# design.net
KiCad netlist of a schematic drawn in Altium Designer
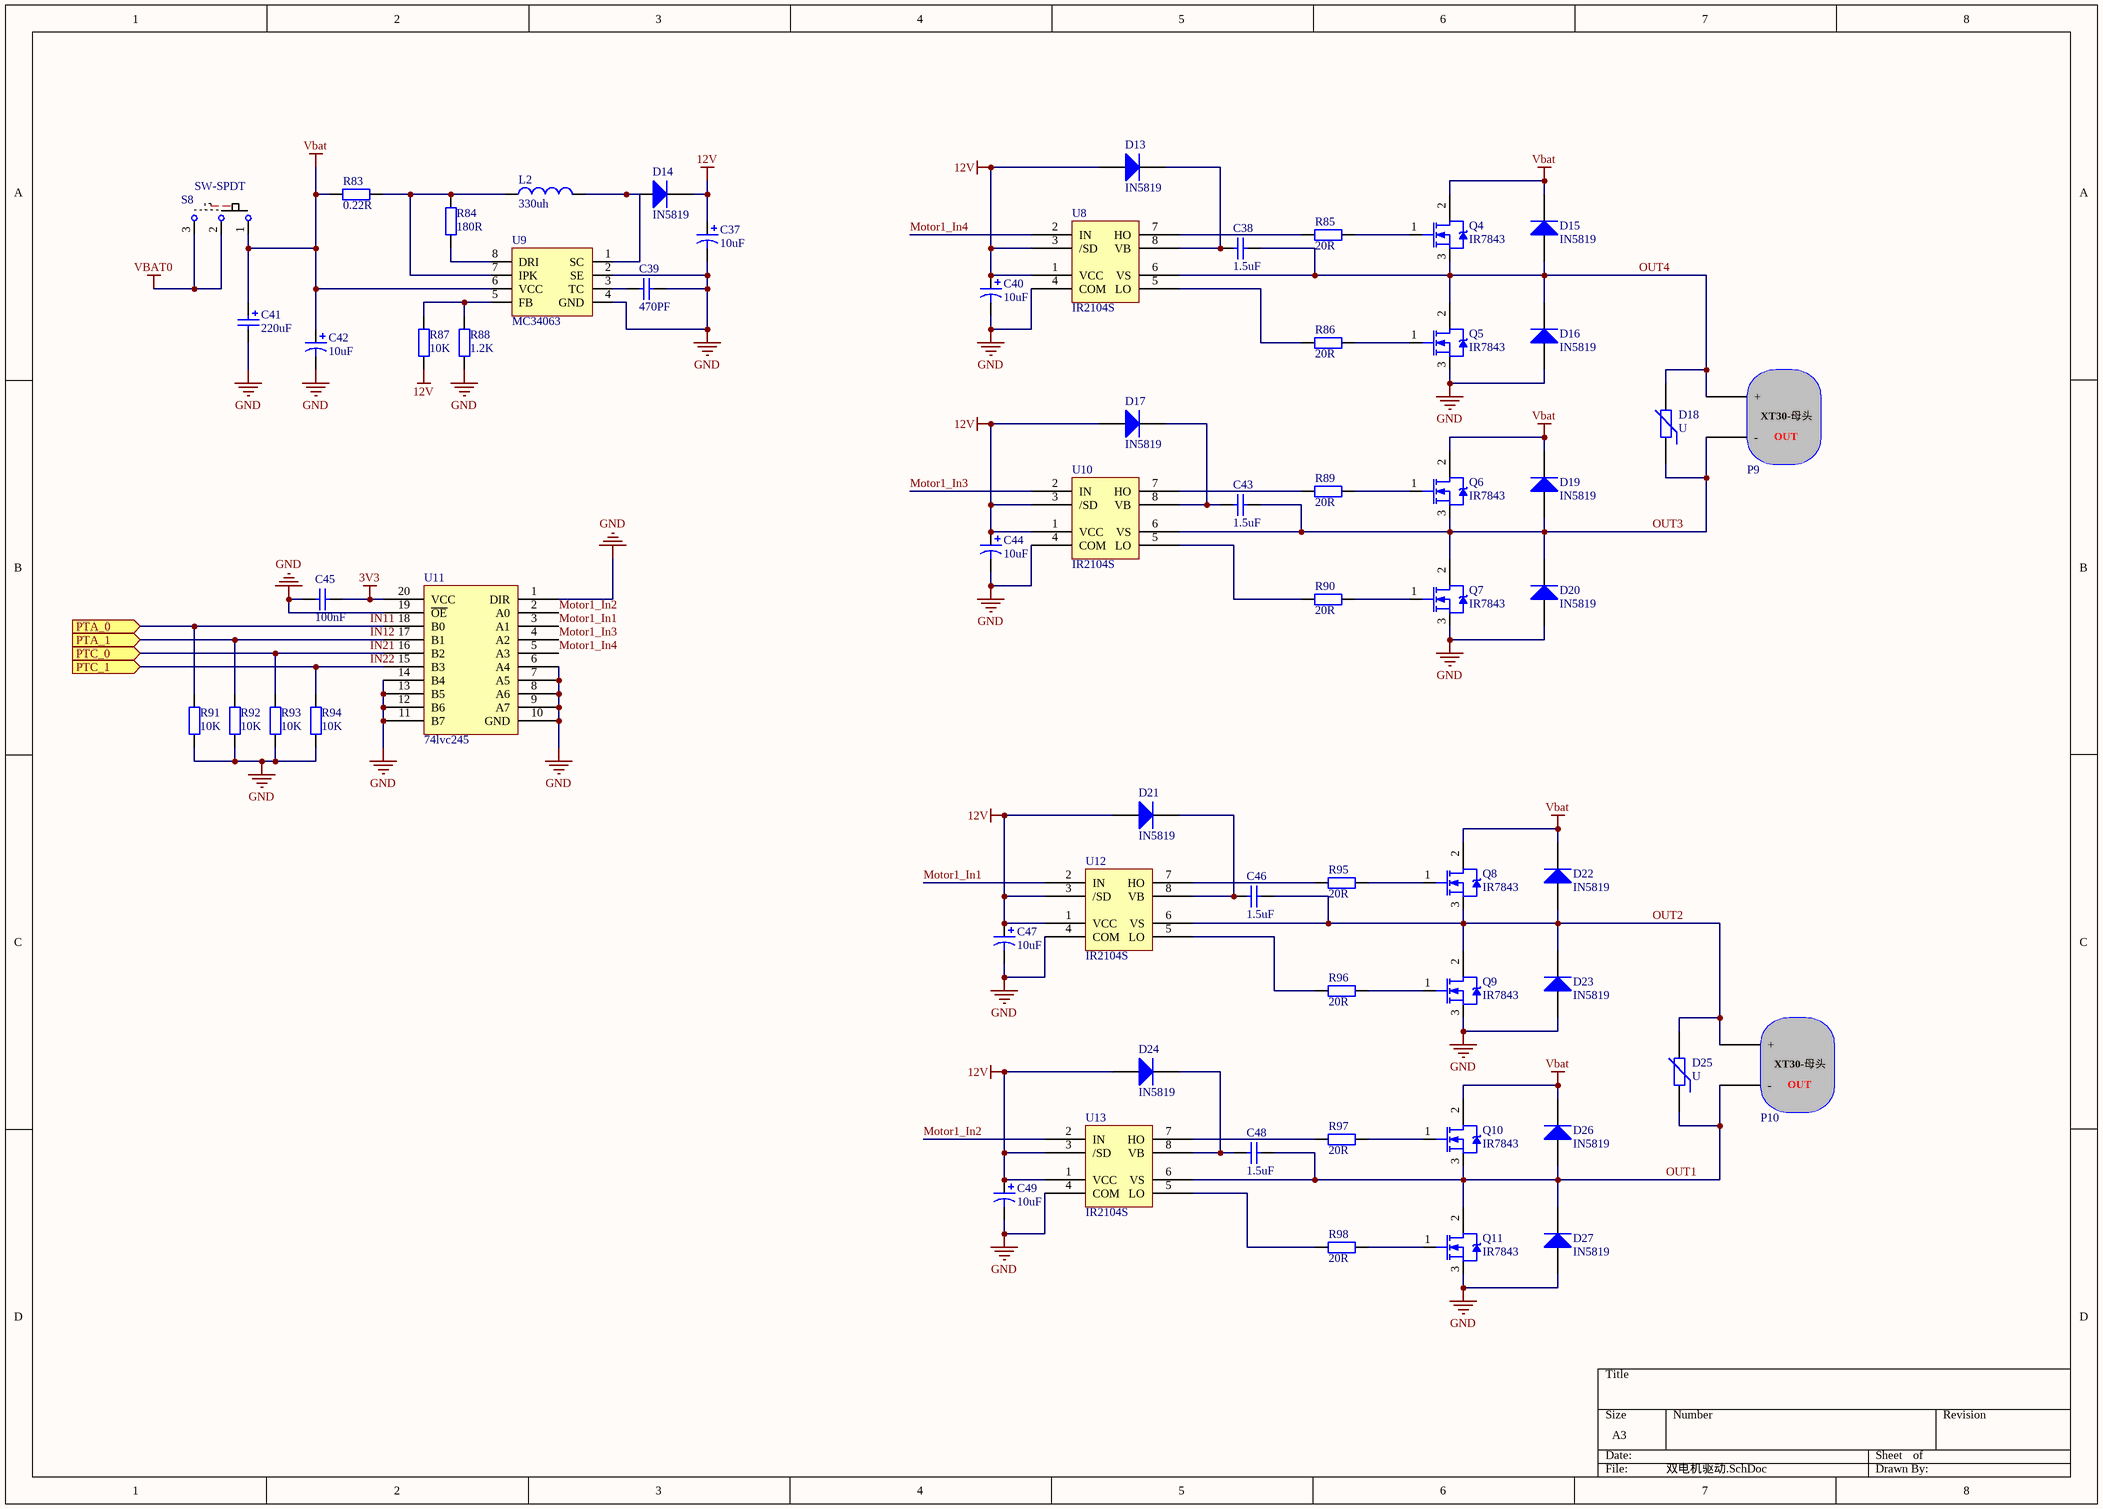
[diagram p0: 双电机驱动.SchDoc]

(export (version "E")
  (design (tool "Eeschema 10.0.6"))
  (components
    (comp (ref "C37")
      (value "10uF")
      (footprint "1206C")
      (description "Polarized Capacitor (Radial)")
      (fields (field (name "PUBLISHER") "Altium Limited"))
      (libsource (lib "MOS motor driving module ") (part "Cap Pol1"))
    )
    (comp (ref "C38")
      (value "1.5uF")
      (footprint "0805(2012)")
      (description "Capacitor")
      (fields (field (name "PUBLISHER") "Altium Limited"))
      (libsource (lib "MOS motor driving module ") (part "Cap"))
    )
    (comp (ref "C39")
      (value "470PF")
      (footprint "0805(2012)")
      (description "Capacitor")
      (fields (field (name "PUBLISHER") "Altium Limited"))
      (libsource (lib "MOS motor driving module ") (part "Cap"))
    )
    (comp (ref "C40")
      (value "10uF")
      (footprint "1206C")
      (description "Polarized Capacitor (Radial)")
      (fields (field (name "PUBLISHER") "Altium Limited"))
      (libsource (lib "MOS motor driving module ") (part "Cap Pol1"))
    )
    (comp (ref "C41")
      (value "220uF")
      (footprint "AEC_D6.3")
      (description "Polarized Capacitor (Radial)")
      (libsource (lib "Landzo电源模块V3.0") (part "Cap Pol1"))
    )
    (comp (ref "C42")
      (value "10uF")
      (footprint "1206C")
      (description "Polarized Capacitor (Radial)")
      (fields (field (name "PUBLISHER") "Altium Limited"))
      (libsource (lib "MOS motor driving module ") (part "Cap Pol1"))
    )
    (comp (ref "C43")
      (value "1.5uF")
      (footprint "0805(2012)")
      (description "Capacitor")
      (fields (field (name "PUBLISHER") "Altium Limited"))
      (libsource (lib "MOS motor driving module ") (part "Cap"))
    )
    (comp (ref "C44")
      (value "10uF")
      (footprint "1206C")
      (description "Polarized Capacitor (Radial)")
      (fields (field (name "PUBLISHER") "Altium Limited"))
      (libsource (lib "MOS motor driving module ") (part "Cap Pol1"))
    )
    (comp (ref "C45")
      (value "100nF")
      (footprint "0805")
      (description "Capacitor")
      (libsource (lib "Landzo电源模块V3.0") (part "Cap"))
    )
    (comp (ref "C46")
      (value "1.5uF")
      (footprint "0805(2012)")
      (description "Capacitor")
      (fields (field (name "PUBLISHER") "Altium Limited"))
      (libsource (lib "MOS motor driving module ") (part "Cap"))
    )
    (comp (ref "C47")
      (value "10uF")
      (footprint "1206C")
      (description "Polarized Capacitor (Radial)")
      (fields (field (name "PUBLISHER") "Altium Limited"))
      (libsource (lib "MOS motor driving module ") (part "Cap Pol1"))
    )
    (comp (ref "C48")
      (value "1.5uF")
      (footprint "0805(2012)")
      (description "Capacitor")
      (fields (field (name "PUBLISHER") "Altium Limited"))
      (libsource (lib "MOS motor driving module ") (part "Cap"))
    )
    (comp (ref "C49")
      (value "10uF")
      (footprint "1206C")
      (description "Polarized Capacitor (Radial)")
      (fields (field (name "PUBLISHER") "Altium Limited"))
      (libsource (lib "MOS motor driving module ") (part "Cap Pol1"))
    )
    (comp (ref "D13")
      (value "IN5819")
      (footprint "Diode-1206")
      (description "Default Diode")
      (libsource (lib "MOS motor driving module ") (part "Diode"))
    )
    (comp (ref "D14")
      (value "IN5819")
      (footprint "SMB")
      (description "Default Diode")
      (libsource (lib "MOS motor driving module ") (part "Diode"))
    )
    (comp (ref "D15")
      (value "IN5819")
      (footprint "SMB")
      (description "Default Diode")
      (libsource (lib "MOS motor driving module ") (part "Diode"))
    )
    (comp (ref "D16")
      (value "IN5819")
      (footprint "SMB")
      (description "Default Diode")
      (libsource (lib "MOS motor driving module ") (part "Diode"))
    )
    (comp (ref "D17")
      (value "IN5819")
      (footprint "Diode-1206")
      (description "Default Diode")
      (libsource (lib "MOS motor driving module ") (part "Diode"))
    )
    (comp (ref "D18")
      (value "U")
      (footprint "0805(2012)")
      (description "Varistor (Voltage-Sensitive Resistor)")
      (fields (field (name "PUBLISHER") "Altium Limited"))
      (libsource (lib "MOS motor driving module ") (part "Res Varistor"))
    )
    (comp (ref "D19")
      (value "IN5819")
      (footprint "SMB")
      (description "Default Diode")
      (libsource (lib "MOS motor driving module ") (part "Diode"))
    )
    (comp (ref "D20")
      (value "IN5819")
      (footprint "SMB")
      (description "Default Diode")
      (libsource (lib "MOS motor driving module ") (part "Diode"))
    )
    (comp (ref "D21")
      (value "IN5819")
      (footprint "Diode-1206")
      (description "Default Diode")
      (libsource (lib "MOS motor driving module ") (part "Diode"))
    )
    (comp (ref "D22")
      (value "IN5819")
      (footprint "SMB")
      (description "Default Diode")
      (libsource (lib "MOS motor driving module ") (part "Diode"))
    )
    (comp (ref "D23")
      (value "IN5819")
      (footprint "SMB")
      (description "Default Diode")
      (libsource (lib "MOS motor driving module ") (part "Diode"))
    )
    (comp (ref "D24")
      (value "IN5819")
      (footprint "Diode-1206")
      (description "Default Diode")
      (libsource (lib "MOS motor driving module ") (part "Diode"))
    )
    (comp (ref "D25")
      (value "U")
      (footprint "0805(2012)")
      (description "Varistor (Voltage-Sensitive Resistor)")
      (fields (field (name "PUBLISHER") "Altium Limited"))
      (libsource (lib "MOS motor driving module ") (part "Res Varistor"))
    )
    (comp (ref "D26")
      (value "IN5819")
      (footprint "SMB")
      (description "Default Diode")
      (libsource (lib "MOS motor driving module ") (part "Diode"))
    )
    (comp (ref "D27")
      (value "IN5819")
      (footprint "SMB")
      (description "Default Diode")
      (libsource (lib "MOS motor driving module ") (part "Diode"))
    )
    (comp (ref "L2")
      (value "330uh")
      (footprint "电感8*8_0")
      (description "Inductor")
      (fields (field (name "PUBLISHER") "Altium Limited"))
      (libsource (lib "MOS motor driving module ") (part "Inductor"))
    )
    (comp (ref "P9") (value "XT30-母-pcb") (footprint "XT30-垂直") (libsource (lib "我的原理图库") (part "XT30-母头")))
    (comp (ref "P10") (value "XT30-母-pcb") (footprint "XT30-垂直") (libsource (lib "我的原理图库") (part "XT30-母头")))
    (comp (ref "Q4")
      (value "IR7843")
      (footprint "LR7843_0")
      (description "N-Channel Power MOSFET")
      (fields (field (name "PUBLISHER") "Altium Limited"))
      (libsource (lib "MOS motor driving module ") (part "NMOS-2"))
    )
    (comp (ref "Q5")
      (value "IR7843")
      (footprint "LR7843_0")
      (description "N-Channel Power MOSFET")
      (fields (field (name "PUBLISHER") "Altium Limited"))
      (libsource (lib "MOS motor driving module ") (part "NMOS-2"))
    )
    (comp (ref "Q6")
      (value "IR7843")
      (footprint "LR7843_0")
      (description "N-Channel Power MOSFET")
      (fields (field (name "PUBLISHER") "Altium Limited"))
      (libsource (lib "MOS motor driving module ") (part "NMOS-2"))
    )
    (comp (ref "Q7")
      (value "IR7843")
      (footprint "LR7843_0")
      (description "N-Channel Power MOSFET")
      (fields (field (name "PUBLISHER") "Altium Limited"))
      (libsource (lib "MOS motor driving module ") (part "NMOS-2"))
    )
    (comp (ref "Q8")
      (value "IR7843")
      (footprint "LR7843_0")
      (description "N-Channel Power MOSFET")
      (fields (field (name "PUBLISHER") "Altium Limited"))
      (libsource (lib "MOS motor driving module ") (part "NMOS-2"))
    )
    (comp (ref "Q9")
      (value "IR7843")
      (footprint "LR7843_0")
      (description "N-Channel Power MOSFET")
      (fields (field (name "PUBLISHER") "Altium Limited"))
      (libsource (lib "MOS motor driving module ") (part "NMOS-2"))
    )
    (comp (ref "Q10")
      (value "IR7843")
      (footprint "LR7843_0")
      (description "N-Channel Power MOSFET")
      (fields (field (name "PUBLISHER") "Altium Limited"))
      (libsource (lib "MOS motor driving module ") (part "NMOS-2"))
    )
    (comp (ref "Q11")
      (value "IR7843")
      (footprint "LR7843_0")
      (description "N-Channel Power MOSFET")
      (fields (field (name "PUBLISHER") "Altium Limited"))
      (libsource (lib "MOS motor driving module ") (part "NMOS-2"))
    )
    (comp (ref "R83")
      (value "0.22R")
      (footprint "0805")
      (description "Resistor")
      (libsource (lib "") (part "Res_3"))
    )
    (comp (ref "R84")
      (value "180R")
      (footprint "0805")
      (description "Resistor")
      (libsource (lib "") (part "Res_1"))
    )
    (comp (ref "R85")
      (value "20R")
      (footprint "0805")
      (description "Resistor")
      (libsource (lib "Landzo电源模块V3.0") (part "Res"))
    )
    (comp (ref "R86")
      (value "20R")
      (footprint "0805")
      (description "Resistor")
      (libsource (lib "Landzo电源模块V3.0") (part "Res"))
    )
    (comp (ref "R87")
      (value "10K")
      (footprint "0805")
      (description "Resistor")
      (libsource (lib "") (part "Res_2"))
    )
    (comp (ref "R88")
      (value "1.2K")
      (footprint "0805")
      (description "Resistor")
      (libsource (lib "") (part "Res_2"))
    )
    (comp (ref "R89")
      (value "20R")
      (footprint "0805")
      (description "Resistor")
      (libsource (lib "Landzo电源模块V3.0") (part "Res"))
    )
    (comp (ref "R90")
      (value "20R")
      (footprint "0805")
      (description "Resistor")
      (libsource (lib "Landzo电源模块V3.0") (part "Res"))
    )
    (comp (ref "R91")
      (value "10K")
      (footprint "0805")
      (description "Resistor")
      (libsource (lib "") (part "Res_1"))
    )
    (comp (ref "R92")
      (value "10K")
      (footprint "0805")
      (description "Resistor")
      (libsource (lib "") (part "Res_1"))
    )
    (comp (ref "R93")
      (value "10K")
      (footprint "0805")
      (description "Resistor")
      (libsource (lib "") (part "Res_1"))
    )
    (comp (ref "R94")
      (value "10K")
      (footprint "0805")
      (description "Resistor")
      (libsource (lib "") (part "Res_1"))
    )
    (comp (ref "R95")
      (value "20R")
      (footprint "0805")
      (description "Resistor")
      (libsource (lib "Landzo电源模块V3.0") (part "Res"))
    )
    (comp (ref "R96")
      (value "20R")
      (footprint "0805")
      (description "Resistor")
      (libsource (lib "Landzo电源模块V3.0") (part "Res"))
    )
    (comp (ref "R97")
      (value "20R")
      (footprint "0805")
      (description "Resistor")
      (libsource (lib "Landzo电源模块V3.0") (part "Res"))
    )
    (comp (ref "R98")
      (value "20R")
      (footprint "0805")
      (description "Resistor")
      (libsource (lib "Landzo电源模块V3.0") (part "Res"))
    )
    (comp (ref "S8")
      (value "SW-SPDT")
      (footprint "SWICH_2")
      (description "SPDT Subminiature Toggle Switch, Right Angle Mounting, Vertical Actuation")
      (libsource (lib "MOS motor driving module ") (part "SW-SPDT"))
    )
    (comp (ref "U8")
      (value "IR2104S")
      (footprint "IR2104")
      (libsource (lib "MOS motor driving module ") (part "Component_1_1"))
    )
    (comp (ref "U9")
      (value "MC34063")
      (footprint "MC34063")
      (libsource (lib "MOS motor driving module ") (part "74HC00"))
    )
    (comp (ref "U10")
      (value "IR2104S")
      (footprint "IR2104")
      (libsource (lib "MOS motor driving module ") (part "Component_1_1"))
    )
    (comp (ref "U11")
      (value "74lvc245")
      (footprint "74lvc245 TSSOP")
      (description "8位5伏转3.3伏电平转换芯片")
      (libsource (lib "MOS motor driving module ") (part "74lvc245"))
    )
    (comp (ref "U12")
      (value "IR2104S")
      (footprint "IR2104")
      (libsource (lib "MOS motor driving module ") (part "Component_1_1"))
    )
    (comp (ref "U13")
      (value "IR2104S")
      (footprint "IR2104")
      (libsource (lib "MOS motor driving module ") (part "Component_1_1"))
    )
  )
  (nets
    (net (code "1") (name "/IN11") (class "Default")
      (node (ref "R91") (pin "2") (pinfunction "2_2") (pintype "passive"))
      (node (ref "U11") (pin "18") (pinfunction "B0_18") (pintype "passive"))
    )
    (net (code "2") (name "/IN12") (class "Default")
      (node (ref "R92") (pin "2") (pinfunction "2_2") (pintype "passive"))
      (node (ref "U11") (pin "17") (pinfunction "B1_17") (pintype "passive"))
    )
    (net (code "3") (name "/IN21") (class "Default")
      (node (ref "R93") (pin "2") (pinfunction "2_2") (pintype "passive"))
      (node (ref "U11") (pin "16") (pinfunction "B2_16") (pintype "passive"))
    )
    (net (code "4") (name "/IN22") (class "Default")
      (node (ref "R94") (pin "2") (pinfunction "2_2") (pintype "passive"))
      (node (ref "U11") (pin "15") (pinfunction "B3_15") (pintype "passive"))
    )
    (net (code "5") (name "/Motor1_In1") (class "Default")
      (node (ref "U11") (pin "3") (pinfunction "A1_3") (pintype "passive"))
      (node (ref "U12") (pin "2") (pinfunction "IN_2") (pintype "passive"))
    )
    (net (code "6") (name "/Motor1_In2") (class "Default")
      (node (ref "U11") (pin "2") (pinfunction "A0_2") (pintype "passive"))
      (node (ref "U13") (pin "2") (pinfunction "IN_2") (pintype "passive"))
    )
    (net (code "7") (name "/Motor1_In3") (class "Default")
      (node (ref "U10") (pin "2") (pinfunction "IN_2") (pintype "passive"))
      (node (ref "U11") (pin "4") (pinfunction "A2_4") (pintype "passive"))
    )
    (net (code "8") (name "/Motor1_In4") (class "Default")
      (node (ref "U11") (pin "5") (pinfunction "A3_5") (pintype "passive"))
      (node (ref "U8") (pin "2") (pinfunction "IN_2") (pintype "passive"))
    )
    (net (code "9") (name "/OUT1") (class "Default")
      (node (ref "C48") (pin "2") (pinfunction "2_2") (pintype "passive"))
      (node (ref "D25") (pin "1") (pinfunction "1_1") (pintype "passive"))
      (node (ref "D26") (pin "1") (pinfunction "A_1") (pintype "passive"))
      (node (ref "D27") (pin "2") (pinfunction "K_2") (pintype "passive"))
      (node (ref "P10") (pin "1") (pinfunction "-_1") (pintype "passive"))
      (node (ref "Q10") (pin "3") (pinfunction "S_3") (pintype "passive"))
      (node (ref "Q11") (pin "2") (pinfunction "D_2") (pintype "passive"))
      (node (ref "U13") (pin "6") (pinfunction "VS_6") (pintype "passive"))
    )
    (net (code "10") (name "/OUT2") (class "Default")
      (node (ref "C46") (pin "2") (pinfunction "2_2") (pintype "passive"))
      (node (ref "D22") (pin "1") (pinfunction "A_1") (pintype "passive"))
      (node (ref "D23") (pin "2") (pinfunction "K_2") (pintype "passive"))
      (node (ref "D25") (pin "2") (pinfunction "2_2") (pintype "passive"))
      (node (ref "P10") (pin "0") (pinfunction "+_0") (pintype "passive"))
      (node (ref "Q8") (pin "3") (pinfunction "S_3") (pintype "passive"))
      (node (ref "Q9") (pin "2") (pinfunction "D_2") (pintype "passive"))
      (node (ref "U12") (pin "6") (pinfunction "VS_6") (pintype "passive"))
    )
    (net (code "11") (name "/OUT3") (class "Default")
      (node (ref "C43") (pin "2") (pinfunction "2_2") (pintype "passive"))
      (node (ref "D18") (pin "1") (pinfunction "1_1") (pintype "passive"))
      (node (ref "D19") (pin "1") (pinfunction "A_1") (pintype "passive"))
      (node (ref "D20") (pin "2") (pinfunction "K_2") (pintype "passive"))
      (node (ref "P9") (pin "1") (pinfunction "-_1") (pintype "passive"))
      (node (ref "Q6") (pin "3") (pinfunction "S_3") (pintype "passive"))
      (node (ref "Q7") (pin "2") (pinfunction "D_2") (pintype "passive"))
      (node (ref "U10") (pin "6") (pinfunction "VS_6") (pintype "passive"))
    )
    (net (code "12") (name "/OUT4") (class "Default")
      (node (ref "C38") (pin "2") (pinfunction "2_2") (pintype "passive"))
      (node (ref "D15") (pin "1") (pinfunction "A_1") (pintype "passive"))
      (node (ref "D16") (pin "2") (pinfunction "K_2") (pintype "passive"))
      (node (ref "D18") (pin "2") (pinfunction "2_2") (pintype "passive"))
      (node (ref "P9") (pin "0") (pinfunction "+_0") (pintype "passive"))
      (node (ref "Q4") (pin "3") (pinfunction "S_3") (pintype "passive"))
      (node (ref "Q5") (pin "2") (pinfunction "D_2") (pintype "passive"))
      (node (ref "U8") (pin "6") (pinfunction "VS_6") (pintype "passive"))
    )
    (net (code "13") (name "3V3") (class "Default")
      (node (ref "C45") (pin "2") (pinfunction "2_2") (pintype "passive"))
      (node (ref "U11") (pin "20") (pinfunction "VCC_20") (pintype "passive"))
    )
    (net (code "14") (name "12V") (class "Default")
      (node (ref "C37") (pin "1") (pinfunction "1_1") (pintype "passive"))
      (node (ref "C40") (pin "1") (pinfunction "1_1") (pintype "passive"))
      (node (ref "C44") (pin "1") (pinfunction "1_1") (pintype "passive"))
      (node (ref "C47") (pin "1") (pinfunction "1_1") (pintype "passive"))
      (node (ref "C49") (pin "1") (pinfunction "1_1") (pintype "passive"))
      (node (ref "D13") (pin "1") (pinfunction "A_1") (pintype "passive"))
      (node (ref "D14") (pin "2") (pinfunction "K_2") (pintype "passive"))
      (node (ref "D17") (pin "1") (pinfunction "A_1") (pintype "passive"))
      (node (ref "D21") (pin "1") (pinfunction "A_1") (pintype "passive"))
      (node (ref "D24") (pin "1") (pinfunction "A_1") (pintype "passive"))
      (node (ref "R87") (pin "2") (pinfunction "2_2") (pintype "passive"))
      (node (ref "U10") (pin "1") (pinfunction "VCC_1") (pintype "passive"))
      (node (ref "U10") (pin "3") (pinfunction "/SD_3") (pintype "passive"))
      (node (ref "U12") (pin "1") (pinfunction "VCC_1") (pintype "passive"))
      (node (ref "U12") (pin "3") (pinfunction "/SD_3") (pintype "passive"))
      (node (ref "U13") (pin "1") (pinfunction "VCC_1") (pintype "passive"))
      (node (ref "U13") (pin "3") (pinfunction "/SD_3") (pintype "passive"))
      (node (ref "U8") (pin "1") (pinfunction "VCC_1") (pintype "passive"))
      (node (ref "U8") (pin "3") (pinfunction "/SD_3") (pintype "passive"))
    )
    (net (code "15") (name "GND") (class "Default")
      (node (ref "C37") (pin "2") (pinfunction "2_2") (pintype "passive"))
      (node (ref "C39") (pin "1") (pinfunction "1_1") (pintype "passive"))
      (node (ref "C40") (pin "2") (pinfunction "2_2") (pintype "passive"))
      (node (ref "C41") (pin "2") (pinfunction "2_2") (pintype "passive"))
      (node (ref "C42") (pin "2") (pinfunction "2_2") (pintype "passive"))
      (node (ref "C44") (pin "2") (pinfunction "2_2") (pintype "passive"))
      (node (ref "C45") (pin "1") (pinfunction "1_1") (pintype "passive"))
      (node (ref "C47") (pin "2") (pinfunction "2_2") (pintype "passive"))
      (node (ref "C49") (pin "2") (pinfunction "2_2") (pintype "passive"))
      (node (ref "D16") (pin "1") (pinfunction "A_1") (pintype "passive"))
      (node (ref "D20") (pin "1") (pinfunction "A_1") (pintype "passive"))
      (node (ref "D23") (pin "1") (pinfunction "A_1") (pintype "passive"))
      (node (ref "D27") (pin "1") (pinfunction "A_1") (pintype "passive"))
      (node (ref "Q11") (pin "3") (pinfunction "S_3") (pintype "passive"))
      (node (ref "Q5") (pin "3") (pinfunction "S_3") (pintype "passive"))
      (node (ref "Q7") (pin "3") (pinfunction "S_3") (pintype "passive"))
      (node (ref "Q9") (pin "3") (pinfunction "S_3") (pintype "passive"))
      (node (ref "R88") (pin "2") (pinfunction "2_2") (pintype "passive"))
      (node (ref "R91") (pin "1") (pinfunction "1_1") (pintype "passive"))
      (node (ref "R92") (pin "1") (pinfunction "1_1") (pintype "passive"))
      (node (ref "R93") (pin "1") (pinfunction "1_1") (pintype "passive"))
      (node (ref "R94") (pin "1") (pinfunction "1_1") (pintype "passive"))
      (node (ref "U10") (pin "4") (pinfunction "COM_4") (pintype "passive"))
      (node (ref "U11") (pin "1") (pinfunction "DIR_1") (pintype "passive"))
      (node (ref "U11") (pin "10") (pinfunction "GND_10") (pintype "passive"))
      (node (ref "U11") (pin "11") (pinfunction "B7_11") (pintype "passive"))
      (node (ref "U11") (pin "12") (pinfunction "B6_12") (pintype "passive"))
      (node (ref "U11") (pin "13") (pinfunction "B5_13") (pintype "passive"))
      (node (ref "U11") (pin "14") (pinfunction "B4_14") (pintype "passive"))
      (node (ref "U11") (pin "19") (pinfunction "~{OE}_19") (pintype "passive"))
      (node (ref "U11") (pin "6") (pinfunction "A4_6") (pintype "passive"))
      (node (ref "U11") (pin "7") (pinfunction "A5_7") (pintype "passive"))
      (node (ref "U11") (pin "8") (pinfunction "A6_8") (pintype "passive"))
      (node (ref "U11") (pin "9") (pinfunction "A7_9") (pintype "passive"))
      (node (ref "U12") (pin "4") (pinfunction "COM_4") (pintype "passive"))
      (node (ref "U13") (pin "4") (pinfunction "COM_4") (pintype "passive"))
      (node (ref "U8") (pin "4") (pinfunction "COM_4") (pintype "passive"))
      (node (ref "U9") (pin "2") (pinfunction "SE_2") (pintype "passive"))
      (node (ref "U9") (pin "4") (pinfunction "GND_4") (pintype "passive"))
    )
    (net (code "16") (name "Net-(D13-K)") (class "Default")
      (node (ref "C38") (pin "1") (pinfunction "1_1") (pintype "passive"))
      (node (ref "D13") (pin "2") (pinfunction "K_2") (pintype "passive"))
      (node (ref "U8") (pin "8") (pinfunction "VB_8") (pintype "passive"))
    )
    (net (code "17") (name "Net-(D14-A)") (class "Default")
      (node (ref "D14") (pin "1") (pinfunction "A_1") (pintype "passive"))
      (node (ref "L2") (pin "2") (pinfunction "2_2") (pintype "passive"))
      (node (ref "U9") (pin "1") (pinfunction "SC_1") (pintype "passive"))
    )
    (net (code "18") (name "Net-(D17-K)") (class "Default")
      (node (ref "C43") (pin "1") (pinfunction "1_1") (pintype "passive"))
      (node (ref "D17") (pin "2") (pinfunction "K_2") (pintype "passive"))
      (node (ref "U10") (pin "8") (pinfunction "VB_8") (pintype "passive"))
    )
    (net (code "19") (name "Net-(D21-K)") (class "Default")
      (node (ref "C46") (pin "1") (pinfunction "1_1") (pintype "passive"))
      (node (ref "D21") (pin "2") (pinfunction "K_2") (pintype "passive"))
      (node (ref "U12") (pin "8") (pinfunction "VB_8") (pintype "passive"))
    )
    (net (code "20") (name "Net-(D24-K)") (class "Default")
      (node (ref "C48") (pin "1") (pinfunction "1_1") (pintype "passive"))
      (node (ref "D24") (pin "2") (pinfunction "K_2") (pintype "passive"))
      (node (ref "U13") (pin "8") (pinfunction "VB_8") (pintype "passive"))
    )
    (net (code "21") (name "Net-(Q4-G)") (class "Default")
      (node (ref "Q4") (pin "1") (pinfunction "G_1") (pintype "passive"))
      (node (ref "R85") (pin "2") (pinfunction "2_2") (pintype "passive"))
    )
    (net (code "22") (name "Net-(Q5-G)") (class "Default")
      (node (ref "Q5") (pin "1") (pinfunction "G_1") (pintype "passive"))
      (node (ref "R86") (pin "2") (pinfunction "2_2") (pintype "passive"))
    )
    (net (code "23") (name "Net-(Q6-G)") (class "Default")
      (node (ref "Q6") (pin "1") (pinfunction "G_1") (pintype "passive"))
      (node (ref "R89") (pin "2") (pinfunction "2_2") (pintype "passive"))
    )
    (net (code "24") (name "Net-(Q7-G)") (class "Default")
      (node (ref "Q7") (pin "1") (pinfunction "G_1") (pintype "passive"))
      (node (ref "R90") (pin "2") (pinfunction "2_2") (pintype "passive"))
    )
    (net (code "25") (name "Net-(Q8-G)") (class "Default")
      (node (ref "Q8") (pin "1") (pinfunction "G_1") (pintype "passive"))
      (node (ref "R95") (pin "2") (pinfunction "2_2") (pintype "passive"))
    )
    (net (code "26") (name "Net-(Q9-G)") (class "Default")
      (node (ref "Q9") (pin "1") (pinfunction "G_1") (pintype "passive"))
      (node (ref "R96") (pin "2") (pinfunction "2_2") (pintype "passive"))
    )
    (net (code "27") (name "Net-(Q10-G)") (class "Default")
      (node (ref "Q10") (pin "1") (pinfunction "G_1") (pintype "passive"))
      (node (ref "R97") (pin "2") (pinfunction "2_2") (pintype "passive"))
    )
    (net (code "28") (name "Net-(Q11-G)") (class "Default")
      (node (ref "Q11") (pin "1") (pinfunction "G_1") (pintype "passive"))
      (node (ref "R98") (pin "2") (pinfunction "2_2") (pintype "passive"))
    )
    (net (code "29") (name "Net-(U8-HO)") (class "Default")
      (node (ref "R85") (pin "1") (pinfunction "1_1") (pintype "passive"))
      (node (ref "U8") (pin "7") (pinfunction "HO_7") (pintype "passive"))
    )
    (net (code "30") (name "Net-(U8-LO)") (class "Default")
      (node (ref "R86") (pin "1") (pinfunction "1_1") (pintype "passive"))
      (node (ref "U8") (pin "5") (pinfunction "LO_5") (pintype "passive"))
    )
    (net (code "31") (name "Net-(U9-DRI)") (class "Default")
      (node (ref "R84") (pin "1") (pinfunction "1_1") (pintype "passive"))
      (node (ref "U9") (pin "8") (pinfunction "DRI_8") (pintype "passive"))
    )
    (net (code "32") (name "Net-(U9-FB)") (class "Default")
      (node (ref "R87") (pin "1") (pinfunction "1_1") (pintype "passive"))
      (node (ref "R88") (pin "1") (pinfunction "1_1") (pintype "passive"))
      (node (ref "U9") (pin "5") (pinfunction "FB_5") (pintype "passive"))
    )
    (net (code "33") (name "Net-(U9-IPK)") (class "Default")
      (node (ref "L2") (pin "1") (pinfunction "1_1") (pintype "passive"))
      (node (ref "R83") (pin "1") (pinfunction "1_1") (pintype "passive"))
      (node (ref "R84") (pin "2") (pinfunction "2_2") (pintype "passive"))
      (node (ref "U9") (pin "7") (pinfunction "IPK_7") (pintype "passive"))
    )
    (net (code "34") (name "Net-(U9-TC)") (class "Default")
      (node (ref "C39") (pin "2") (pinfunction "2_2") (pintype "passive"))
      (node (ref "U9") (pin "3") (pinfunction "TC_3") (pintype "passive"))
    )
    (net (code "35") (name "Net-(U10-HO)") (class "Default")
      (node (ref "R89") (pin "1") (pinfunction "1_1") (pintype "passive"))
      (node (ref "U10") (pin "7") (pinfunction "HO_7") (pintype "passive"))
    )
    (net (code "36") (name "Net-(U10-LO)") (class "Default")
      (node (ref "R90") (pin "1") (pinfunction "1_1") (pintype "passive"))
      (node (ref "U10") (pin "5") (pinfunction "LO_5") (pintype "passive"))
    )
    (net (code "37") (name "Net-(U12-HO)") (class "Default")
      (node (ref "R95") (pin "1") (pinfunction "1_1") (pintype "passive"))
      (node (ref "U12") (pin "7") (pinfunction "HO_7") (pintype "passive"))
    )
    (net (code "38") (name "Net-(U12-LO)") (class "Default")
      (node (ref "R96") (pin "1") (pinfunction "1_1") (pintype "passive"))
      (node (ref "U12") (pin "5") (pinfunction "LO_5") (pintype "passive"))
    )
    (net (code "39") (name "Net-(U13-HO)") (class "Default")
      (node (ref "R97") (pin "1") (pinfunction "1_1") (pintype "passive"))
      (node (ref "U13") (pin "7") (pinfunction "HO_7") (pintype "passive"))
    )
    (net (code "40") (name "Net-(U13-LO)") (class "Default")
      (node (ref "R98") (pin "1") (pinfunction "1_1") (pintype "passive"))
      (node (ref "U13") (pin "5") (pinfunction "LO_5") (pintype "passive"))
    )
    (net (code "41") (name "VBAT0") (class "Default")
      (node (ref "S8") (pin "2") (pinfunction "2_2") (pintype "passive"))
      (node (ref "S8") (pin "3") (pinfunction "3_3") (pintype "passive"))
    )
    (net (code "42") (name "Vbat") (class "Default")
      (node (ref "C41") (pin "1") (pinfunction "1_1") (pintype "passive"))
      (node (ref "C42") (pin "1") (pinfunction "1_1") (pintype "passive"))
      (node (ref "D15") (pin "2") (pinfunction "K_2") (pintype "passive"))
      (node (ref "D19") (pin "2") (pinfunction "K_2") (pintype "passive"))
      (node (ref "D22") (pin "2") (pinfunction "K_2") (pintype "passive"))
      (node (ref "D26") (pin "2") (pinfunction "K_2") (pintype "passive"))
      (node (ref "Q10") (pin "2") (pinfunction "D_2") (pintype "passive"))
      (node (ref "Q4") (pin "2") (pinfunction "D_2") (pintype "passive"))
      (node (ref "Q6") (pin "2") (pinfunction "D_2") (pintype "passive"))
      (node (ref "Q8") (pin "2") (pinfunction "D_2") (pintype "passive"))
      (node (ref "R83") (pin "2") (pinfunction "2_2") (pintype "passive"))
      (node (ref "S8") (pin "1") (pinfunction "1_1") (pintype "passive"))
      (node (ref "U9") (pin "6") (pinfunction "VCC_6") (pintype "passive"))
    )
  )
)
